# Tarocco-Lite.net
KiCad netlist of a schematic drawn in EAGLE
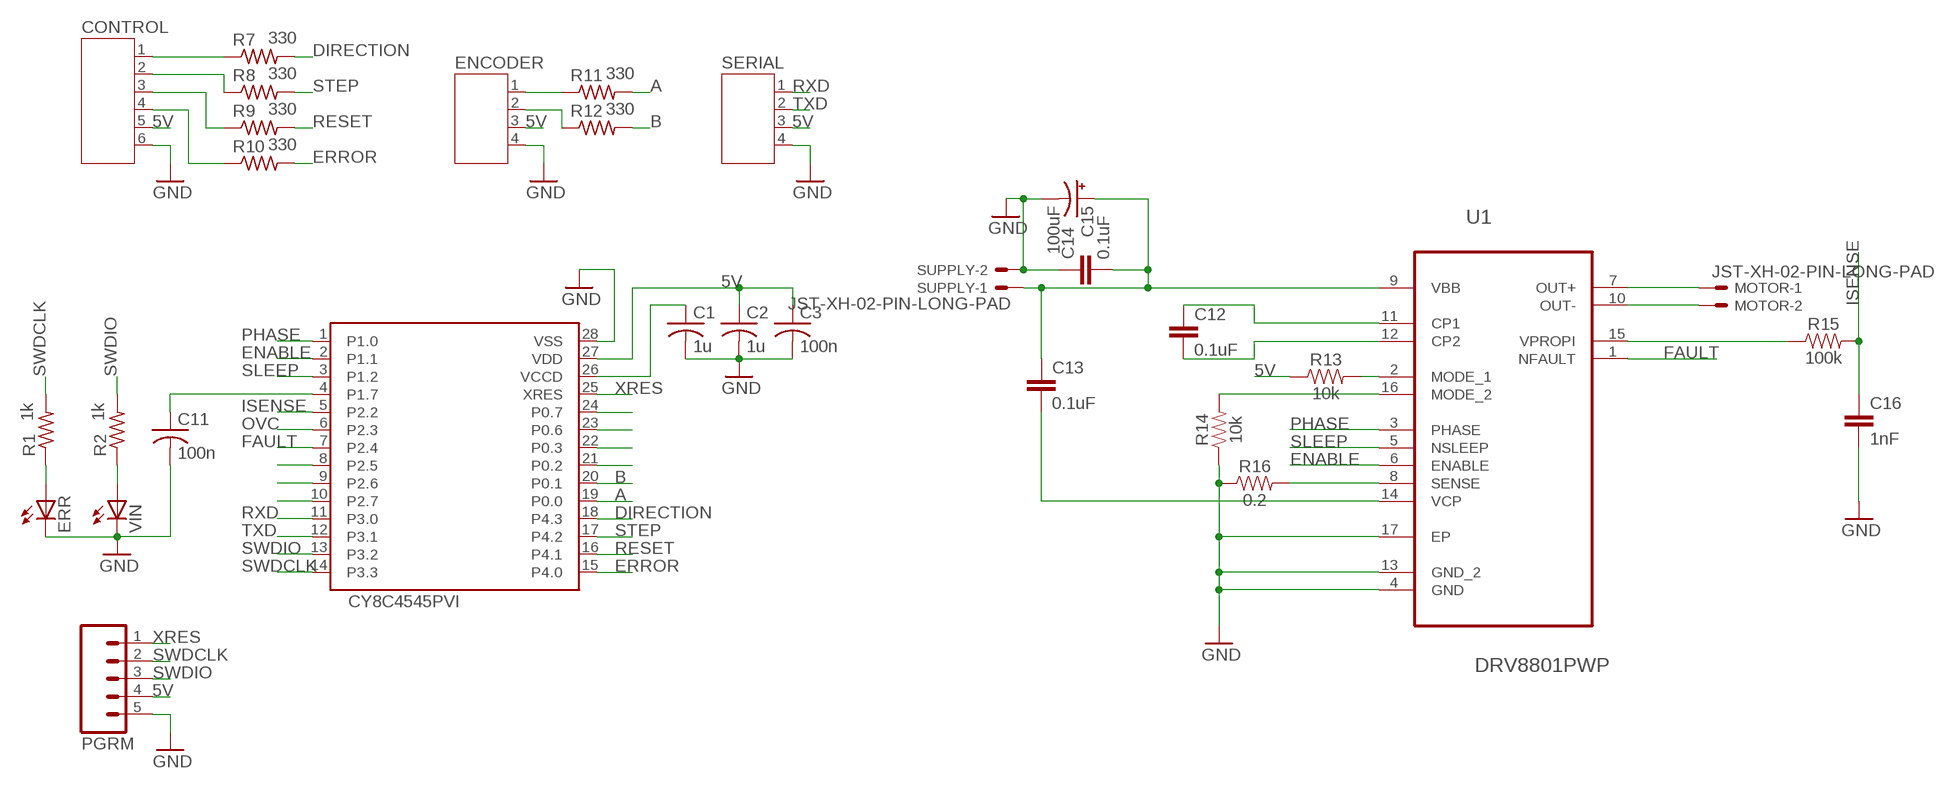
[diagram p0: schematic, sheet 1]

(export (version "E")
  (design (tool "Eeschema 10.0.6"))
  (components
    (comp (ref "C1")
      (value "1u")
      (footprint "eagle-import:C0603")
      (libsource (lib "eagle-import") (part "C-USC0603"))
    )
    (comp (ref "C2")
      (value "1u")
      (footprint "eagle-import:C0603")
      (libsource (lib "eagle-import") (part "C-USC0603"))
    )
    (comp (ref "C3")
      (value "100n")
      (footprint "eagle-import:C0603")
      (libsource (lib "eagle-import") (part "C-USC0603"))
    )
    (comp (ref "C11")
      (value "100n")
      (footprint "eagle-import:C0603")
      (libsource (lib "eagle-import") (part "C-USC0603"))
    )
    (comp (ref "C12")
      (value "0.1uF")
      (footprint "eagle-import:0603")
      (libsource (lib "eagle-import") (part "0.1UF-0603-100V-10%"))
    )
    (comp (ref "C13")
      (value "0.1uF")
      (footprint "eagle-import:0603")
      (libsource (lib "eagle-import") (part "0.1UF-0603-25V-(+80/-20%)"))
    )
    (comp (ref "C14")
      (value "0.1uF")
      (footprint "eagle-import:0603")
      (libsource (lib "eagle-import") (part "0.1UF-0603-25V-(+80/-20%)"))
    )
    (comp (ref "C15")
      (value "100uF")
      (footprint "eagle-import:PANASONIC_D")
      (libsource (lib "eagle-import") (part "100UF-POLAR-25V-20%(ELEC)"))
    )
    (comp (ref "C16")
      (value "1nF")
      (footprint "eagle-import:0603")
      (libsource (lib "eagle-import") (part "1.0NF/1000PF-0603-50V-10%"))
    )
    (comp (ref "CONTROL")
      (value "JST-PH6")
      (footprint "eagle-import:JST-PH6")
      (libsource (lib "eagle-import") (part "JST-PH6"))
    )
    (comp (ref "ENCODER")
      (value "JST-PH4")
      (footprint "eagle-import:JST-PH4")
      (libsource (lib "eagle-import") (part "JST-PH4"))
    )
    (comp (ref "ERR")
      (value "LEDCHIP-LED0603")
      (footprint "eagle-import:CHIP-LED0603")
      (libsource (lib "eagle-import") (part "LEDCHIP-LED0603"))
    )
    (comp (ref "IC1")
      (value "CY8C4545PVI")
      (footprint "eagle-import:SSOP28")
      (libsource (lib "eagle-import") (part "CY8C4545PVI"))
    )
    (comp (ref "MOTOR")
      (value "JST-XH-02-PIN-LONG-PAD")
      (footprint "eagle-import:JST-XH-02-PACKAGE-LONG-PAD")
      (libsource (lib "eagle-import") (part "JST-XH-02-PIN-LONG-PAD"))
    )
    (comp (ref "PGRM")
      (value "M05SMD2")
      (footprint "eagle-import:1X05-1MM-RA")
      (libsource (lib "eagle-import") (part "M05SMD2"))
    )
    (comp (ref "R1")
      (value "1k")
      (footprint "eagle-import:R0603")
      (libsource (lib "eagle-import") (part "R-US_R0603"))
    )
    (comp (ref "R2")
      (value "1k")
      (footprint "eagle-import:R0603")
      (libsource (lib "eagle-import") (part "R-US_R0603"))
    )
    (comp (ref "R7")
      (value "330")
      (footprint "eagle-import:R0603")
      (libsource (lib "eagle-import") (part "R-US_R0603"))
    )
    (comp (ref "R8")
      (value "330")
      (footprint "eagle-import:R0603")
      (libsource (lib "eagle-import") (part "R-US_R0603"))
    )
    (comp (ref "R9")
      (value "330")
      (footprint "eagle-import:R0603")
      (libsource (lib "eagle-import") (part "R-US_R0603"))
    )
    (comp (ref "R10")
      (value "330")
      (footprint "eagle-import:R0603")
      (libsource (lib "eagle-import") (part "R-US_R0603"))
    )
    (comp (ref "R11")
      (value "330")
      (footprint "eagle-import:R0603")
      (libsource (lib "eagle-import") (part "R-US_R0603"))
    )
    (comp (ref "R12")
      (value "330")
      (footprint "eagle-import:R0603")
      (libsource (lib "eagle-import") (part "R-US_R0603"))
    )
    (comp (ref "R13")
      (value "10k")
      (footprint "eagle-import:0603")
      (libsource (lib "eagle-import") (part "10KOHM-0603-1/10W-1%"))
    )
    (comp (ref "R14")
      (value "10k")
      (footprint "eagle-import:0603")
      (libsource (lib "eagle-import") (part "10KOHM-0603-1/10W-1%"))
    )
    (comp (ref "R15")
      (value "100k")
      (footprint "eagle-import:0603")
      (libsource (lib "eagle-import") (part "100KOHM-0603-1/10W-1%"))
    )
    (comp (ref "R16")
      (value "0.2")
      (footprint "eagle-import:1210")
      (libsource (lib "eagle-import") (part "0.1OHM-1210-1/2W-1%"))
    )
    (comp (ref "SERIAL")
      (value "JST-PH4")
      (footprint "eagle-import:JST-PH4")
      (libsource (lib "eagle-import") (part "JST-PH4"))
    )
    (comp (ref "SUPPLY")
      (value "JST-XH-02-PIN-LONG-PAD")
      (footprint "eagle-import:JST-XH-02-PACKAGE-LONG-PAD")
      (libsource (lib "eagle-import") (part "JST-XH-02-PIN-LONG-PAD"))
    )
    (comp (ref "U1")
      (value "DRV8801PWP")
      (footprint "eagle-import:SOP65P640X120-17N")
      (fields (field (name "MF") "Texas Instruments"))
      (libsource (lib "eagle-import") (part "DRV8801PWP"))
    )
    (comp (ref "VIN")
      (value "LEDCHIP-LED0603")
      (footprint "eagle-import:CHIP-LED0603")
      (libsource (lib "eagle-import") (part "LEDCHIP-LED0603"))
    )
  )
  (nets
    (net (code "1") (name "/5V") (class "Default")
      (node (ref "C2") (pin "1") (pinfunction "1_1") (pintype "passive"))
      (node (ref "C3") (pin "1") (pinfunction "1_1") (pintype "passive"))
      (node (ref "CONTROL") (pin "5") (pinfunction "5_5") (pintype "passive"))
      (node (ref "ENCODER") (pin "3") (pinfunction "3_3") (pintype "passive"))
      (node (ref "IC1") (pin "27") (pinfunction "VDD_27") (pintype "power_in"))
      (node (ref "PGRM") (pin "4") (pinfunction "4_4") (pintype "passive"))
      (node (ref "R13") (pin "1") (pinfunction "1_1") (pintype "passive"))
      (node (ref "SERIAL") (pin "3") (pinfunction "3_3") (pintype "passive"))
    )
    (net (code "2") (name "/A") (class "Default")
      (node (ref "IC1") (pin "19") (pinfunction "P0.0_19") (pintype "bidirectional"))
      (node (ref "R11") (pin "2") (pinfunction "2_2") (pintype "passive"))
    )
    (net (code "3") (name "/B") (class "Default")
      (node (ref "IC1") (pin "20") (pinfunction "P0.1_20") (pintype "bidirectional"))
      (node (ref "R12") (pin "2") (pinfunction "2_2") (pintype "passive"))
    )
    (net (code "4") (name "/DIRECTION") (class "Default")
      (node (ref "IC1") (pin "18") (pinfunction "P4.3_18") (pintype "bidirectional"))
      (node (ref "R7") (pin "2") (pinfunction "2_2") (pintype "passive"))
    )
    (net (code "5") (name "/ENABLE") (class "Default")
      (node (ref "IC1") (pin "2") (pinfunction "P1.1_2") (pintype "bidirectional"))
      (node (ref "U1") (pin "6") (pinfunction "ENABLE_6") (pintype "input"))
    )
    (net (code "6") (name "/ERROR") (class "Default")
      (node (ref "IC1") (pin "15") (pinfunction "P4.0_15") (pintype "bidirectional"))
      (node (ref "R10") (pin "2") (pinfunction "2_2") (pintype "passive"))
    )
    (net (code "7") (name "/FAULT") (class "Default")
      (node (ref "IC1") (pin "7") (pinfunction "P2.4_7") (pintype "bidirectional"))
      (node (ref "U1") (pin "1") (pinfunction "NFAULT_1") (pintype "output"))
    )
    (net (code "8") (name "/ISENSE") (class "Default")
      (node (ref "C16") (pin "1") (pinfunction "1_1") (pintype "passive"))
      (node (ref "IC1") (pin "5") (pinfunction "P2.2_5") (pintype "bidirectional"))
      (node (ref "R15") (pin "2") (pinfunction "2_2") (pintype "passive"))
    )
    (net (code "9") (name "/OVC") (class "Default")
      (node (ref "IC1") (pin "6") (pinfunction "P2.3_6") (pintype "bidirectional"))
    )
    (net (code "10") (name "/PHASE") (class "Default")
      (node (ref "IC1") (pin "1") (pinfunction "P1.0_1") (pintype "bidirectional"))
      (node (ref "U1") (pin "3") (pinfunction "PHASE_3") (pintype "input"))
    )
    (net (code "11") (name "/RESET") (class "Default")
      (node (ref "IC1") (pin "16") (pinfunction "P4.1_16") (pintype "bidirectional"))
      (node (ref "R9") (pin "2") (pinfunction "2_2") (pintype "passive"))
    )
    (net (code "12") (name "/RXD") (class "Default")
      (node (ref "IC1") (pin "11") (pinfunction "P3.0_11") (pintype "bidirectional"))
      (node (ref "SERIAL") (pin "1") (pinfunction "1_1") (pintype "passive"))
    )
    (net (code "13") (name "/SLEEP") (class "Default")
      (node (ref "IC1") (pin "3") (pinfunction "P1.2_3") (pintype "bidirectional"))
      (node (ref "U1") (pin "5") (pinfunction "NSLEEP_5") (pintype "input"))
    )
    (net (code "14") (name "/STEP") (class "Default")
      (node (ref "IC1") (pin "17") (pinfunction "P4.2_17") (pintype "bidirectional"))
      (node (ref "R8") (pin "2") (pinfunction "2_2") (pintype "passive"))
    )
    (net (code "15") (name "/SWDCLK") (class "Default")
      (node (ref "IC1") (pin "14") (pinfunction "P3.3_14") (pintype "bidirectional"))
      (node (ref "PGRM") (pin "2") (pinfunction "2_2") (pintype "passive"))
      (node (ref "R1") (pin "2") (pinfunction "2_2") (pintype "passive"))
    )
    (net (code "16") (name "/SWDIO") (class "Default")
      (node (ref "IC1") (pin "13") (pinfunction "P3.2_13") (pintype "bidirectional"))
      (node (ref "PGRM") (pin "3") (pinfunction "3_3") (pintype "passive"))
      (node (ref "R2") (pin "2") (pinfunction "2_2") (pintype "passive"))
    )
    (net (code "17") (name "/TXD") (class "Default")
      (node (ref "IC1") (pin "12") (pinfunction "P3.1_12") (pintype "bidirectional"))
      (node (ref "SERIAL") (pin "2") (pinfunction "2_2") (pintype "passive"))
    )
    (net (code "18") (name "/XRES") (class "Default")
      (node (ref "IC1") (pin "25") (pinfunction "XRES_25") (pintype "bidirectional"))
      (node (ref "PGRM") (pin "1") (pinfunction "1_1") (pintype "passive"))
    )
    (net (code "19") (name "GND") (class "Default")
      (node (ref "C1") (pin "2") (pinfunction "2_2") (pintype "passive"))
      (node (ref "C11") (pin "2") (pinfunction "2_2") (pintype "passive"))
      (node (ref "C14") (pin "1") (pinfunction "1_1") (pintype "passive"))
      (node (ref "C15") (pin "-") (pinfunction "-_-") (pintype "passive"))
      (node (ref "C16") (pin "2") (pinfunction "2_2") (pintype "passive"))
      (node (ref "C2") (pin "2") (pinfunction "2_2") (pintype "passive"))
      (node (ref "C3") (pin "2") (pinfunction "2_2") (pintype "passive"))
      (node (ref "CONTROL") (pin "6") (pinfunction "6_6") (pintype "passive"))
      (node (ref "ENCODER") (pin "4") (pinfunction "4_4") (pintype "passive"))
      (node (ref "ERR") (pin "C") (pinfunction "C_C") (pintype "passive"))
      (node (ref "IC1") (pin "28") (pinfunction "VSS_28") (pintype "power_in"))
      (node (ref "PGRM") (pin "5") (pinfunction "5_5") (pintype "passive"))
      (node (ref "R14") (pin "1") (pinfunction "1_1") (pintype "passive"))
      (node (ref "R16") (pin "1") (pinfunction "1_1") (pintype "passive"))
      (node (ref "SERIAL") (pin "4") (pinfunction "4_4") (pintype "passive"))
      (node (ref "SUPPLY") (pin "2") (pinfunction "S_2") (pintype "passive"))
      (node (ref "U1") (pin "13") (pinfunction "GND_2_13") (pintype "passive"))
      (node (ref "U1") (pin "17") (pinfunction "EP_17") (pintype "passive"))
      (node (ref "U1") (pin "4") (pinfunction "GND_4") (pintype "passive"))
      (node (ref "VIN") (pin "C") (pinfunction "C_C") (pintype "passive"))
    )
    (net (code "20") (name "Net-(CONTROL-Pad1)") (class "Default")
      (node (ref "CONTROL") (pin "1") (pinfunction "1_1") (pintype "passive"))
      (node (ref "R7") (pin "1") (pinfunction "1_1") (pintype "passive"))
    )
    (net (code "21") (name "Net-(CONTROL-Pad2)") (class "Default")
      (node (ref "CONTROL") (pin "2") (pinfunction "2_2") (pintype "passive"))
      (node (ref "R8") (pin "1") (pinfunction "1_1") (pintype "passive"))
    )
    (net (code "22") (name "Net-(CONTROL-Pad3)") (class "Default")
      (node (ref "CONTROL") (pin "3") (pinfunction "3_3") (pintype "passive"))
      (node (ref "R9") (pin "1") (pinfunction "1_1") (pintype "passive"))
    )
    (net (code "23") (name "Net-(CONTROL-Pad4)") (class "Default")
      (node (ref "CONTROL") (pin "4") (pinfunction "4_4") (pintype "passive"))
      (node (ref "R10") (pin "1") (pinfunction "1_1") (pintype "passive"))
    )
    (net (code "24") (name "Net-(ENCODER-Pad1)") (class "Default")
      (node (ref "ENCODER") (pin "1") (pinfunction "1_1") (pintype "passive"))
      (node (ref "R11") (pin "1") (pinfunction "1_1") (pintype "passive"))
    )
    (net (code "25") (name "Net-(ENCODER-Pad2)") (class "Default")
      (node (ref "ENCODER") (pin "2") (pinfunction "2_2") (pintype "passive"))
      (node (ref "R12") (pin "1") (pinfunction "1_1") (pintype "passive"))
    )
    (net (code "26") (name "Net-(ERR-PadA)") (class "Default")
      (node (ref "ERR") (pin "A") (pinfunction "A_A") (pintype "passive"))
      (node (ref "R1") (pin "1") (pinfunction "1_1") (pintype "passive"))
    )
    (net (code "27") (name "Net-(IC1-P1.7)") (class "Default")
      (node (ref "C11") (pin "1") (pinfunction "1_1") (pintype "passive"))
      (node (ref "IC1") (pin "4") (pinfunction "P1.7_4") (pintype "bidirectional"))
    )
    (net (code "28") (name "Net-(IC1-VCCD)") (class "Default")
      (node (ref "C1") (pin "1") (pinfunction "1_1") (pintype "passive"))
      (node (ref "IC1") (pin "26") (pinfunction "VCCD_26") (pintype "power_in"))
    )
    (net (code "29") (name "Net-(MOTORA-S)") (class "Default")
      (node (ref "MOTOR") (pin "1") (pinfunction "S_1") (pintype "passive"))
      (node (ref "U1") (pin "7") (pinfunction "OUT+_7") (pintype "output"))
    )
    (net (code "30") (name "Net-(MOTORB-S)") (class "Default")
      (node (ref "MOTOR") (pin "2") (pinfunction "S_2") (pintype "passive"))
      (node (ref "U1") (pin "10") (pinfunction "OUT-_10") (pintype "output"))
    )
    (net (code "31") (name "Net-(R2-Pad1)") (class "Default")
      (node (ref "R2") (pin "1") (pinfunction "1_1") (pintype "passive"))
      (node (ref "VIN") (pin "A") (pinfunction "A_A") (pintype "passive"))
    )
    (net (code "32") (name "Net-(SUPPLYA-S)") (class "Default")
      (node (ref "C13") (pin "1") (pinfunction "1_1") (pintype "passive"))
      (node (ref "C14") (pin "2") (pinfunction "2_2") (pintype "passive"))
      (node (ref "C15") (pin "+") (pinfunction "+_+") (pintype "passive"))
      (node (ref "SUPPLY") (pin "1") (pinfunction "S_1") (pintype "passive"))
      (node (ref "U1") (pin "9") (pinfunction "VBB_9") (pintype "power_in"))
    )
    (net (code "33") (name "Net-(U1-CP1)") (class "Default")
      (node (ref "C12") (pin "1") (pinfunction "1_1") (pintype "passive"))
      (node (ref "U1") (pin "11") (pinfunction "CP1_11") (pintype "input"))
    )
    (net (code "34") (name "Net-(U1-CP2)") (class "Default")
      (node (ref "C12") (pin "2") (pinfunction "2_2") (pintype "passive"))
      (node (ref "U1") (pin "12") (pinfunction "CP2_12") (pintype "input"))
    )
    (net (code "35") (name "Net-(U1-MODE_1)") (class "Default")
      (node (ref "R13") (pin "2") (pinfunction "2_2") (pintype "passive"))
      (node (ref "U1") (pin "2") (pinfunction "MODE_1_2") (pintype "input"))
    )
    (net (code "36") (name "Net-(U1-MODE_2)") (class "Default")
      (node (ref "R14") (pin "2") (pinfunction "2_2") (pintype "passive"))
      (node (ref "U1") (pin "16") (pinfunction "MODE_2_16") (pintype "input"))
    )
    (net (code "37") (name "Net-(U1-SENSE)") (class "Default")
      (node (ref "R16") (pin "2") (pinfunction "2_2") (pintype "passive"))
      (node (ref "U1") (pin "8") (pinfunction "SENSE_8") (pintype "input"))
    )
    (net (code "38") (name "Net-(U1-VCP)") (class "Default")
      (node (ref "C13") (pin "2") (pinfunction "2_2") (pintype "passive"))
      (node (ref "U1") (pin "14") (pinfunction "VCP_14") (pintype "input"))
    )
    (net (code "39") (name "Net-(U1-VPROPI)") (class "Default")
      (node (ref "R15") (pin "1") (pinfunction "1_1") (pintype "passive"))
      (node (ref "U1") (pin "15") (pinfunction "VPROPI_15") (pintype "output"))
    )
    (net (code "40") (name "unconnected-(IC1-P0.2-Pad21)") (class "Default")
      (node (ref "IC1") (pin "21") (pinfunction "P0.2_21") (pintype "bidirectional"))
    )
    (net (code "41") (name "unconnected-(IC1-P0.3-Pad22)") (class "Default")
      (node (ref "IC1") (pin "22") (pinfunction "P0.3_22") (pintype "bidirectional"))
    )
    (net (code "42") (name "unconnected-(IC1-P0.6-Pad23)") (class "Default")
      (node (ref "IC1") (pin "23") (pinfunction "P0.6_23") (pintype "bidirectional"))
    )
    (net (code "43") (name "unconnected-(IC1-P0.7-Pad24)") (class "Default")
      (node (ref "IC1") (pin "24") (pinfunction "P0.7_24") (pintype "bidirectional"))
    )
    (net (code "44") (name "unconnected-(IC1-P2.5-Pad8)") (class "Default")
      (node (ref "IC1") (pin "8") (pinfunction "P2.5_8") (pintype "bidirectional"))
    )
    (net (code "45") (name "unconnected-(IC1-P2.6-Pad9)") (class "Default")
      (node (ref "IC1") (pin "9") (pinfunction "P2.6_9") (pintype "bidirectional"))
    )
    (net (code "46") (name "unconnected-(IC1-P2.7-Pad10)") (class "Default")
      (node (ref "IC1") (pin "10") (pinfunction "P2.7_10") (pintype "bidirectional"))
    )
  )
)
